# sheet4.net
KiCad netlist of a schematic drawn in Altium Designer
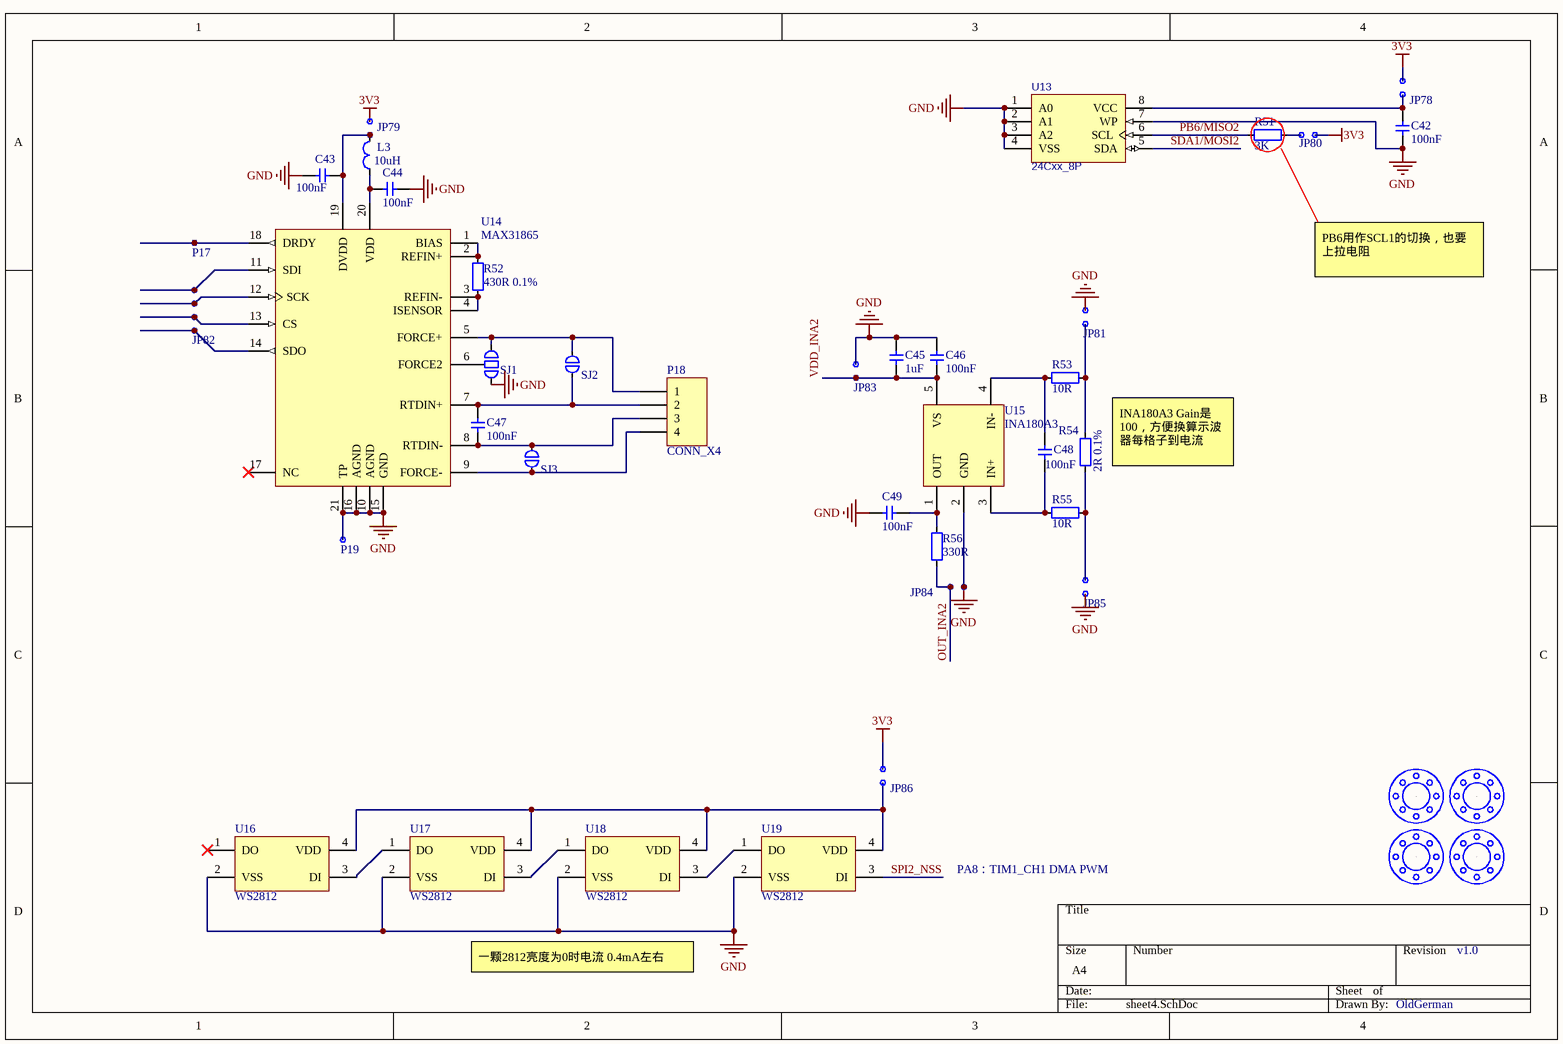
[diagram p0: sheet4.SchDoc]

(export (version "E")
  (design (tool "Eeschema 10.0.6"))
  (components
    (comp (ref "C42")
      (value "100nF")
      (footprint "C0603")
      (description "Capacitor")
      (libsource (lib "ODG_AD_Lib") (part "CAP"))
    )
    (comp (ref "C43")
      (value "100nF")
      (footprint "C0603")
      (description "Capacitor")
      (libsource (lib "ODG_AD_Lib") (part "CAP"))
    )
    (comp (ref "C44")
      (value "100nF")
      (footprint "C0603")
      (description "Capacitor")
      (libsource (lib "ODG_AD_Lib") (part "CAP"))
    )
    (comp (ref "C45")
      (value "1uF")
      (footprint "C0603")
      (description "Capacitor")
      (libsource (lib "ODG_AD_Lib") (part "CAP"))
    )
    (comp (ref "C46")
      (value "100nF")
      (footprint "C0603")
      (description "Capacitor")
      (libsource (lib "ODG_AD_Lib") (part "CAP"))
    )
    (comp (ref "C47")
      (value "100nF")
      (footprint "C0603")
      (description "Capacitor")
      (libsource (lib "ODG_AD_Lib") (part "CAP"))
    )
    (comp (ref "C48")
      (value "100nF")
      (footprint "C0603")
      (description "Capacitor")
      (libsource (lib "ODG_AD_Lib") (part "CAP"))
    )
    (comp (ref "C49")
      (value "100nF")
      (footprint "C0603")
      (description "Capacitor")
      (libsource (lib "ODG_AD_Lib") (part "CAP"))
    )
    (comp (ref "JP78")
      (value "CONN_X2_DOT")
      (footprint "2.54mm_Male_x2")
      (libsource (lib "ODG_AD_Lib") (part "CONN_X2_DOT"))
    )
    (comp (ref "JP79")
      (value "CONN_X2_DOT")
      (footprint "2.54mm_Male_x2")
      (libsource (lib "ODG_AD_Lib") (part "CONN_X2_DOT"))
    )
    (comp (ref "JP80")
      (value "CONN_X2_DOT")
      (footprint "2.54mm_Male_x2")
      (libsource (lib "ODG_AD_Lib") (part "CONN_X2_DOT"))
    )
    (comp (ref "JP81")
      (value "CONN_X2_DOT")
      (footprint "2.54mm_Male_x2")
      (libsource (lib "ODG_AD_Lib") (part "CONN_X2_DOT"))
    )
    (comp (ref "JP82")
      (value "CONN_X4_DOT")
      (footprint "2.54mm_Male_x4")
      (libsource (lib "ODG_AD_Lib") (part "CONN_X4_DOT"))
    )
    (comp (ref "JP83")
      (value "CONN_X2_DOT")
      (footprint "2.54mm_Male_x2")
      (libsource (lib "ODG_AD_Lib") (part "CONN_X2_DOT"))
    )
    (comp (ref "JP84")
      (value "CONN_X2_DOT")
      (footprint "2.54mm_Male_x2")
      (libsource (lib "ODG_AD_Lib") (part "CONN_X2_DOT"))
    )
    (comp (ref "JP85")
      (value "CONN_X2_DOT")
      (footprint "2.54mm_Male_x2")
      (libsource (lib "ODG_AD_Lib") (part "CONN_X2_DOT"))
    )
    (comp (ref "JP86")
      (value "CONN_X2_DOT")
      (footprint "2.54mm_Male_x2")
      (libsource (lib "ODG_AD_Lib") (part "CONN_X2_DOT"))
    )
    (comp (ref "L3")
      (value "10uH")
      (footprint "FER0603")
      (description "贴片叠层电感")
      (libsource (lib "ODG_AD_Lib") (part "inductor_mini"))
    )
    (comp (ref "P17")
      (value "CONN_X1_DOT")
      (footprint "2.54mm_Male_x1")
      (libsource (lib "ODG_AD_Lib") (part "CONN_X1_DOT"))
    )
    (comp (ref "P18")
      (value "CONN_X4")
      (footprint "2.54mm_Male_x4")
      (libsource (lib "ODG_AD_Lib") (part "CONN_X4"))
    )
    (comp (ref "P19")
      (value "CONN_X1_DOT")
      (footprint "2.54mm_Male_x1")
      (libsource (lib "ODG_AD_Lib") (part "CONN_X1_DOT"))
    )
    (comp (ref "R51")
      (value "3K")
      (footprint "R0603")
      (description "Resistor")
      (libsource (lib "ODG_AD_Lib") (part "RES"))
    )
    (comp (ref "R52")
      (value "430R 0.1%")
      (footprint "R0603")
      (description "Resistor")
      (libsource (lib "") (part "RES_2"))
    )
    (comp (ref "R53")
      (value "10R")
      (footprint "R0603")
      (description "Resistor")
      (libsource (lib "ODG_AD_Lib") (part "RES"))
    )
    (comp (ref "R54")
      (value "2R 0.1%")
      (footprint "R0805")
      (description "Resistor")
      (libsource (lib "") (part "RES_1"))
    )
    (comp (ref "R55")
      (value "10R")
      (footprint "R0603")
      (description "Resistor")
      (libsource (lib "ODG_AD_Lib") (part "RES"))
    )
    (comp (ref "R56")
      (value "330R")
      (footprint "R0603")
      (description "Resistor")
      (libsource (lib "") (part "RES_2"))
    )
    (comp (ref "SJ1")
      (value "SJ_3P")
      (footprint "SJ_3P")
      (description "焊接跳线二选一")
      (libsource (lib "ODG_AD_Lib") (part "SJ_3P"))
    )
    (comp (ref "SJ2")
      (value "SJ_2P")
      (footprint "SJ_2P")
      (description "焊接跳线")
      (libsource (lib "ODG_AD_Lib") (part "SJ_2P"))
    )
    (comp (ref "SJ3")
      (value "SJ_2P")
      (footprint "SJ_2P")
      (description "焊接跳线")
      (libsource (lib "ODG_AD_Lib") (part "SJ_2P"))
    )
    (comp (ref "SUN_HOLE1")
      (value "SUN_HOLE")
      (footprint "SUN_HOLE_M3")
      (libsource (lib "ODG_AD_Lib") (part "SUN_HOLE"))
    )
    (comp (ref "SUN_HOLE2")
      (value "SUN_HOLE")
      (footprint "SUN_HOLE_M3")
      (libsource (lib "ODG_AD_Lib") (part "SUN_HOLE"))
    )
    (comp (ref "SUN_HOLE3")
      (value "SUN_HOLE")
      (footprint "SUN_HOLE_M3")
      (libsource (lib "ODG_AD_Lib") (part "SUN_HOLE"))
    )
    (comp (ref "SUN_HOLE4")
      (value "SUN_HOLE")
      (footprint "SUN_HOLE_M3")
      (libsource (lib "ODG_AD_Lib") (part "SUN_HOLE"))
    )
    (comp (ref "U13")
      (value "24Cxx_8P")
      (footprint "ANALOG DEV SOIC-8 R8")
      (libsource (lib "ODG_AD_Lib") (part "24Cxx_8P"))
    )
    (comp (ref "U14")
      (value "MAX31865")
      (footprint "VQFN-20 5x5MM 0.65")
      (libsource (lib "ODG_AD_Lib") (part "MAX31865"))
    )
    (comp (ref "U15")
      (value "INA180A3")
      (footprint "TI SOT-23-5 DBV")
      (description "Low- and High-Side Voltage Output, Current-Sense Amplifiers")
      (libsource (lib "ODG_AD_Lib") (part "INA180Ax"))
    )
    (comp (ref "U16")
      (value "WS2812")
      (footprint "WS2812_2020")
      (libsource (lib "ODG_AD_Lib") (part "WS2812"))
    )
    (comp (ref "U17")
      (value "WS2812")
      (footprint "WS2812_2020")
      (libsource (lib "ODG_AD_Lib") (part "WS2812"))
    )
    (comp (ref "U18")
      (value "WS2812")
      (footprint "WS2812_2020")
      (libsource (lib "ODG_AD_Lib") (part "WS2812"))
    )
    (comp (ref "U19")
      (value "WS2812")
      (footprint "WS2812_2020")
      (libsource (lib "ODG_AD_Lib") (part "WS2812"))
    )
  )
  (nets
    (net (code "1") (name "/OUT_INA2") (class "Default")
      (node (ref "JP84") (pin "1") (pinfunction "1_1") (pintype "passive"))
      (node (ref "R56") (pin "1") (pinfunction "1_1") (pintype "passive"))
    )
    (net (code "2") (name "/PB6{slash}MISO2") (class "Default")
      (node (ref "R51") (pin "1") (pinfunction "1_1") (pintype "passive"))
      (node (ref "U13") (pin "6") (pinfunction "SCL_6") (pintype "input"))
    )
    (net (code "3") (name "/SDA1{slash}MOSI2") (class "Default")
      (node (ref "U13") (pin "5") (pinfunction "SDA_5") (pintype "bidirectional"))
    )
    (net (code "4") (name "/SPI2_NSS") (class "Default")
      (node (ref "U19") (pin "3") (pinfunction "DI_3") (pintype "passive"))
    )
    (net (code "5") (name "/VDD_INA2") (class "Default")
      (node (ref "C45") (pin "1") (pinfunction "1_1") (pintype "passive"))
      (node (ref "C46") (pin "1") (pinfunction "1_1") (pintype "passive"))
      (node (ref "JP83") (pin "2") (pinfunction "2_2") (pintype "passive"))
      (node (ref "U15") (pin "5") (pinfunction "VS_5") (pintype "passive"))
    )
    (net (code "6") (name "3V3") (class "Default")
      (node (ref "JP78") (pin "1") (pinfunction "1_1") (pintype "passive"))
      (node (ref "JP79") (pin "1") (pinfunction "1_1") (pintype "passive"))
      (node (ref "JP80") (pin "2") (pinfunction "2_2") (pintype "passive"))
      (node (ref "JP86") (pin "1") (pinfunction "1_1") (pintype "passive"))
    )
    (net (code "7") (name "GND") (class "Default")
      (node (ref "C42") (pin "2") (pinfunction "2_2") (pintype "passive"))
      (node (ref "C43") (pin "2") (pinfunction "2_2") (pintype "passive"))
      (node (ref "C44") (pin "2") (pinfunction "2_2") (pintype "passive"))
      (node (ref "C45") (pin "2") (pinfunction "2_2") (pintype "passive"))
      (node (ref "C46") (pin "2") (pinfunction "2_2") (pintype "passive"))
      (node (ref "C49") (pin "2") (pinfunction "2_2") (pintype "passive"))
      (node (ref "JP81") (pin "1") (pinfunction "1_1") (pintype "passive"))
      (node (ref "JP83") (pin "1") (pinfunction "1_1") (pintype "passive"))
      (node (ref "JP84") (pin "2") (pinfunction "2_2") (pintype "passive"))
      (node (ref "JP85") (pin "2") (pinfunction "2_2") (pintype "passive"))
      (node (ref "P19") (pin "1") (pinfunction "1_1") (pintype "passive"))
      (node (ref "SJ1") (pin "3") (pinfunction "3_3") (pintype "passive"))
      (node (ref "U13") (pin "1") (pinfunction "A0_1") (pintype "passive"))
      (node (ref "U13") (pin "2") (pinfunction "A1_2") (pintype "passive"))
      (node (ref "U13") (pin "3") (pinfunction "A2_3") (pintype "passive"))
      (node (ref "U13") (pin "4") (pinfunction "VSS_4") (pintype "passive"))
      (node (ref "U13") (pin "7") (pinfunction "WP_7") (pintype "input"))
      (node (ref "U14") (pin "10") (pinfunction "AGND_10") (pintype "passive"))
      (node (ref "U14") (pin "15") (pinfunction "GND_15") (pintype "passive"))
      (node (ref "U14") (pin "16") (pinfunction "AGND_16") (pintype "passive"))
      (node (ref "U14") (pin "21") (pinfunction "TP_21") (pintype "passive"))
      (node (ref "U15") (pin "2") (pinfunction "GND_2") (pintype "passive"))
      (node (ref "U16") (pin "2") (pinfunction "VSS_2") (pintype "passive"))
      (node (ref "U17") (pin "2") (pinfunction "VSS_2") (pintype "passive"))
      (node (ref "U18") (pin "2") (pinfunction "VSS_2") (pintype "passive"))
      (node (ref "U19") (pin "2") (pinfunction "VSS_2") (pintype "passive"))
    )
    (net (code "8") (name "Net-(JP80-Pad1)") (class "Default")
      (node (ref "JP80") (pin "1") (pinfunction "1_1") (pintype "passive"))
      (node (ref "R51") (pin "2") (pinfunction "2_2") (pintype "passive"))
    )
    (net (code "9") (name "Net-(JP81-Pad2)") (class "Default")
      (node (ref "JP81") (pin "2") (pinfunction "2_2") (pintype "passive"))
      (node (ref "R53") (pin "2") (pinfunction "2_2") (pintype "passive"))
      (node (ref "R54") (pin "1") (pinfunction "1_1") (pintype "passive"))
    )
    (net (code "10") (name "Net-(JP85-Pad1)") (class "Default")
      (node (ref "JP85") (pin "1") (pinfunction "1_1") (pintype "passive"))
      (node (ref "R54") (pin "2") (pinfunction "2_2") (pintype "passive"))
      (node (ref "R55") (pin "2") (pinfunction "2_2") (pintype "passive"))
    )
    (net (code "11") (name "Net-(U13-VCC)") (class "Default")
      (node (ref "C42") (pin "1") (pinfunction "1_1") (pintype "passive"))
      (node (ref "JP78") (pin "2") (pinfunction "2_2") (pintype "passive"))
      (node (ref "U13") (pin "8") (pinfunction "VCC_8") (pintype "passive"))
    )
    (net (code "12") (name "Net-(U14-BIAS)") (class "Default")
      (node (ref "R52") (pin "2") (pinfunction "2_2") (pintype "passive"))
      (node (ref "U14") (pin "1") (pinfunction "BIAS_1") (pintype "passive"))
      (node (ref "U14") (pin "2") (pinfunction "REFIN+_2") (pintype "passive"))
    )
    (net (code "13") (name "Net-(U14-CS)") (class "Default")
      (node (ref "JP82") (pin "3") (pinfunction "3_3") (pintype "passive"))
      (node (ref "U14") (pin "13") (pinfunction "CS_13") (pintype "input"))
    )
    (net (code "14") (name "Net-(U14-DRDY)") (class "Default")
      (node (ref "P17") (pin "1") (pinfunction "1_1") (pintype "passive"))
      (node (ref "U14") (pin "18") (pinfunction "DRDY_18") (pintype "output"))
    )
    (net (code "15") (name "Net-(U14-DVDD)") (class "Default")
      (node (ref "C43") (pin "1") (pinfunction "1_1") (pintype "passive"))
      (node (ref "JP79") (pin "2") (pinfunction "2_2") (pintype "passive"))
      (node (ref "L3") (pin "2") (pinfunction "2_2") (pintype "passive"))
      (node (ref "U14") (pin "19") (pinfunction "DVDD_19") (pintype "passive"))
    )
    (net (code "16") (name "Net-(U14-FORCE+)") (class "Default")
      (node (ref "P18") (pin "1") (pinfunction "1_1") (pintype "passive"))
      (node (ref "SJ1") (pin "1") (pinfunction "1_1") (pintype "passive"))
      (node (ref "SJ2") (pin "1") (pinfunction "1_1") (pintype "passive"))
      (node (ref "U14") (pin "5") (pinfunction "FORCE+_5") (pintype "passive"))
    )
    (net (code "17") (name "Net-(U14-FORCE-)") (class "Default")
      (node (ref "P18") (pin "4") (pinfunction "4_4") (pintype "passive"))
      (node (ref "SJ3") (pin "2") (pinfunction "2_2") (pintype "passive"))
      (node (ref "U14") (pin "9") (pinfunction "FORCE-_9") (pintype "passive"))
    )
    (net (code "18") (name "Net-(U14-FORCE2)") (class "Default")
      (node (ref "SJ1") (pin "2") (pinfunction "2_2") (pintype "passive"))
      (node (ref "U14") (pin "6") (pinfunction "FORCE2_6") (pintype "passive"))
    )
    (net (code "19") (name "Net-(U14-ISENSOR)") (class "Default")
      (node (ref "R52") (pin "1") (pinfunction "1_1") (pintype "passive"))
      (node (ref "U14") (pin "3") (pinfunction "REFIN-_3") (pintype "passive"))
      (node (ref "U14") (pin "4") (pinfunction "ISENSOR_4") (pintype "passive"))
    )
    (net (code "20") (name "Net-(U14-RTDIN+)") (class "Default")
      (node (ref "C47") (pin "1") (pinfunction "1_1") (pintype "passive"))
      (node (ref "P18") (pin "2") (pinfunction "2_2") (pintype "passive"))
      (node (ref "SJ2") (pin "2") (pinfunction "2_2") (pintype "passive"))
      (node (ref "U14") (pin "7") (pinfunction "RTDIN+_7") (pintype "passive"))
    )
    (net (code "21") (name "Net-(U14-RTDIN-)") (class "Default")
      (node (ref "C47") (pin "2") (pinfunction "2_2") (pintype "passive"))
      (node (ref "P18") (pin "3") (pinfunction "3_3") (pintype "passive"))
      (node (ref "SJ3") (pin "1") (pinfunction "1_1") (pintype "passive"))
      (node (ref "U14") (pin "8") (pinfunction "RTDIN-_8") (pintype "passive"))
    )
    (net (code "22") (name "Net-(U14-SCK)") (class "Default")
      (node (ref "JP82") (pin "2") (pinfunction "2_2") (pintype "passive"))
      (node (ref "U14") (pin "12") (pinfunction "SCK_12") (pintype "input"))
    )
    (net (code "23") (name "Net-(U14-SDI)") (class "Default")
      (node (ref "JP82") (pin "1") (pinfunction "1_1") (pintype "passive"))
      (node (ref "U14") (pin "11") (pinfunction "SDI_11") (pintype "input"))
    )
    (net (code "24") (name "Net-(U14-SDO)") (class "Default")
      (node (ref "JP82") (pin "4") (pinfunction "4_4") (pintype "passive"))
      (node (ref "U14") (pin "14") (pinfunction "SDO_14") (pintype "output"))
    )
    (net (code "25") (name "Net-(U14-VDD)") (class "Default")
      (node (ref "C44") (pin "1") (pinfunction "1_1") (pintype "passive"))
      (node (ref "L3") (pin "1") (pinfunction "1_1") (pintype "passive"))
      (node (ref "U14") (pin "20") (pinfunction "VDD_20") (pintype "passive"))
    )
    (net (code "26") (name "Net-(U15-IN+)") (class "Default")
      (node (ref "C48") (pin "1") (pinfunction "1_1") (pintype "passive"))
      (node (ref "R55") (pin "1") (pinfunction "1_1") (pintype "passive"))
      (node (ref "U15") (pin "3") (pinfunction "IN+_3") (pintype "power_in"))
    )
    (net (code "27") (name "Net-(U15-IN-)") (class "Default")
      (node (ref "C48") (pin "2") (pinfunction "2_2") (pintype "passive"))
      (node (ref "R53") (pin "1") (pinfunction "1_1") (pintype "passive"))
      (node (ref "U15") (pin "4") (pinfunction "IN-_4") (pintype "passive"))
    )
    (net (code "28") (name "Net-(U15-OUT)") (class "Default")
      (node (ref "C49") (pin "1") (pinfunction "1_1") (pintype "passive"))
      (node (ref "R56") (pin "2") (pinfunction "2_2") (pintype "passive"))
      (node (ref "U15") (pin "1") (pinfunction "OUT_1") (pintype "passive"))
    )
    (net (code "29") (name "Net-(U16-DI)") (class "Default")
      (node (ref "U16") (pin "3") (pinfunction "DI_3") (pintype "passive"))
      (node (ref "U17") (pin "1") (pinfunction "DO_1") (pintype "passive"))
    )
    (net (code "30") (name "Net-(U16-VDD)") (class "Default")
      (node (ref "JP86") (pin "2") (pinfunction "2_2") (pintype "passive"))
      (node (ref "U16") (pin "4") (pinfunction "VDD_4") (pintype "passive"))
      (node (ref "U17") (pin "4") (pinfunction "VDD_4") (pintype "passive"))
      (node (ref "U18") (pin "4") (pinfunction "VDD_4") (pintype "passive"))
      (node (ref "U19") (pin "4") (pinfunction "VDD_4") (pintype "passive"))
    )
    (net (code "31") (name "Net-(U17-DI)") (class "Default")
      (node (ref "U17") (pin "3") (pinfunction "DI_3") (pintype "passive"))
      (node (ref "U18") (pin "1") (pinfunction "DO_1") (pintype "passive"))
    )
    (net (code "32") (name "Net-(U18-DI)") (class "Default")
      (node (ref "U18") (pin "3") (pinfunction "DI_3") (pintype "passive"))
      (node (ref "U19") (pin "1") (pinfunction "DO_1") (pintype "passive"))
    )
    (net (code "33") (name "unconnected-(SUN_HOLE1-Pad1)") (class "Default")
      (node (ref "SUN_HOLE1") (pin "1") (pinfunction "1_1") (pintype "passive"))
    )
    (net (code "34") (name "unconnected-(SUN_HOLE2-Pad1)") (class "Default")
      (node (ref "SUN_HOLE2") (pin "1") (pinfunction "1_1") (pintype "passive"))
    )
    (net (code "35") (name "unconnected-(SUN_HOLE3-Pad1)") (class "Default")
      (node (ref "SUN_HOLE3") (pin "1") (pinfunction "1_1") (pintype "passive"))
    )
    (net (code "36") (name "unconnected-(SUN_HOLE4-Pad1)") (class "Default")
      (node (ref "SUN_HOLE4") (pin "1") (pinfunction "1_1") (pintype "passive"))
    )
    (net (code "37") (name "unconnected-(U14-NC-Pad17)") (class "Default")
      (node (ref "U14") (pin "17") (pinfunction "NC_17") (pintype "passive+no_connect"))
    )
    (net (code "38") (name "unconnected-(U16-DO-Pad1)") (class "Default")
      (node (ref "U16") (pin "1") (pinfunction "DO_1") (pintype "passive+no_connect"))
    )
  )
)
